# dongle.net
KiCad netlist of a schematic drawn in EAGLE
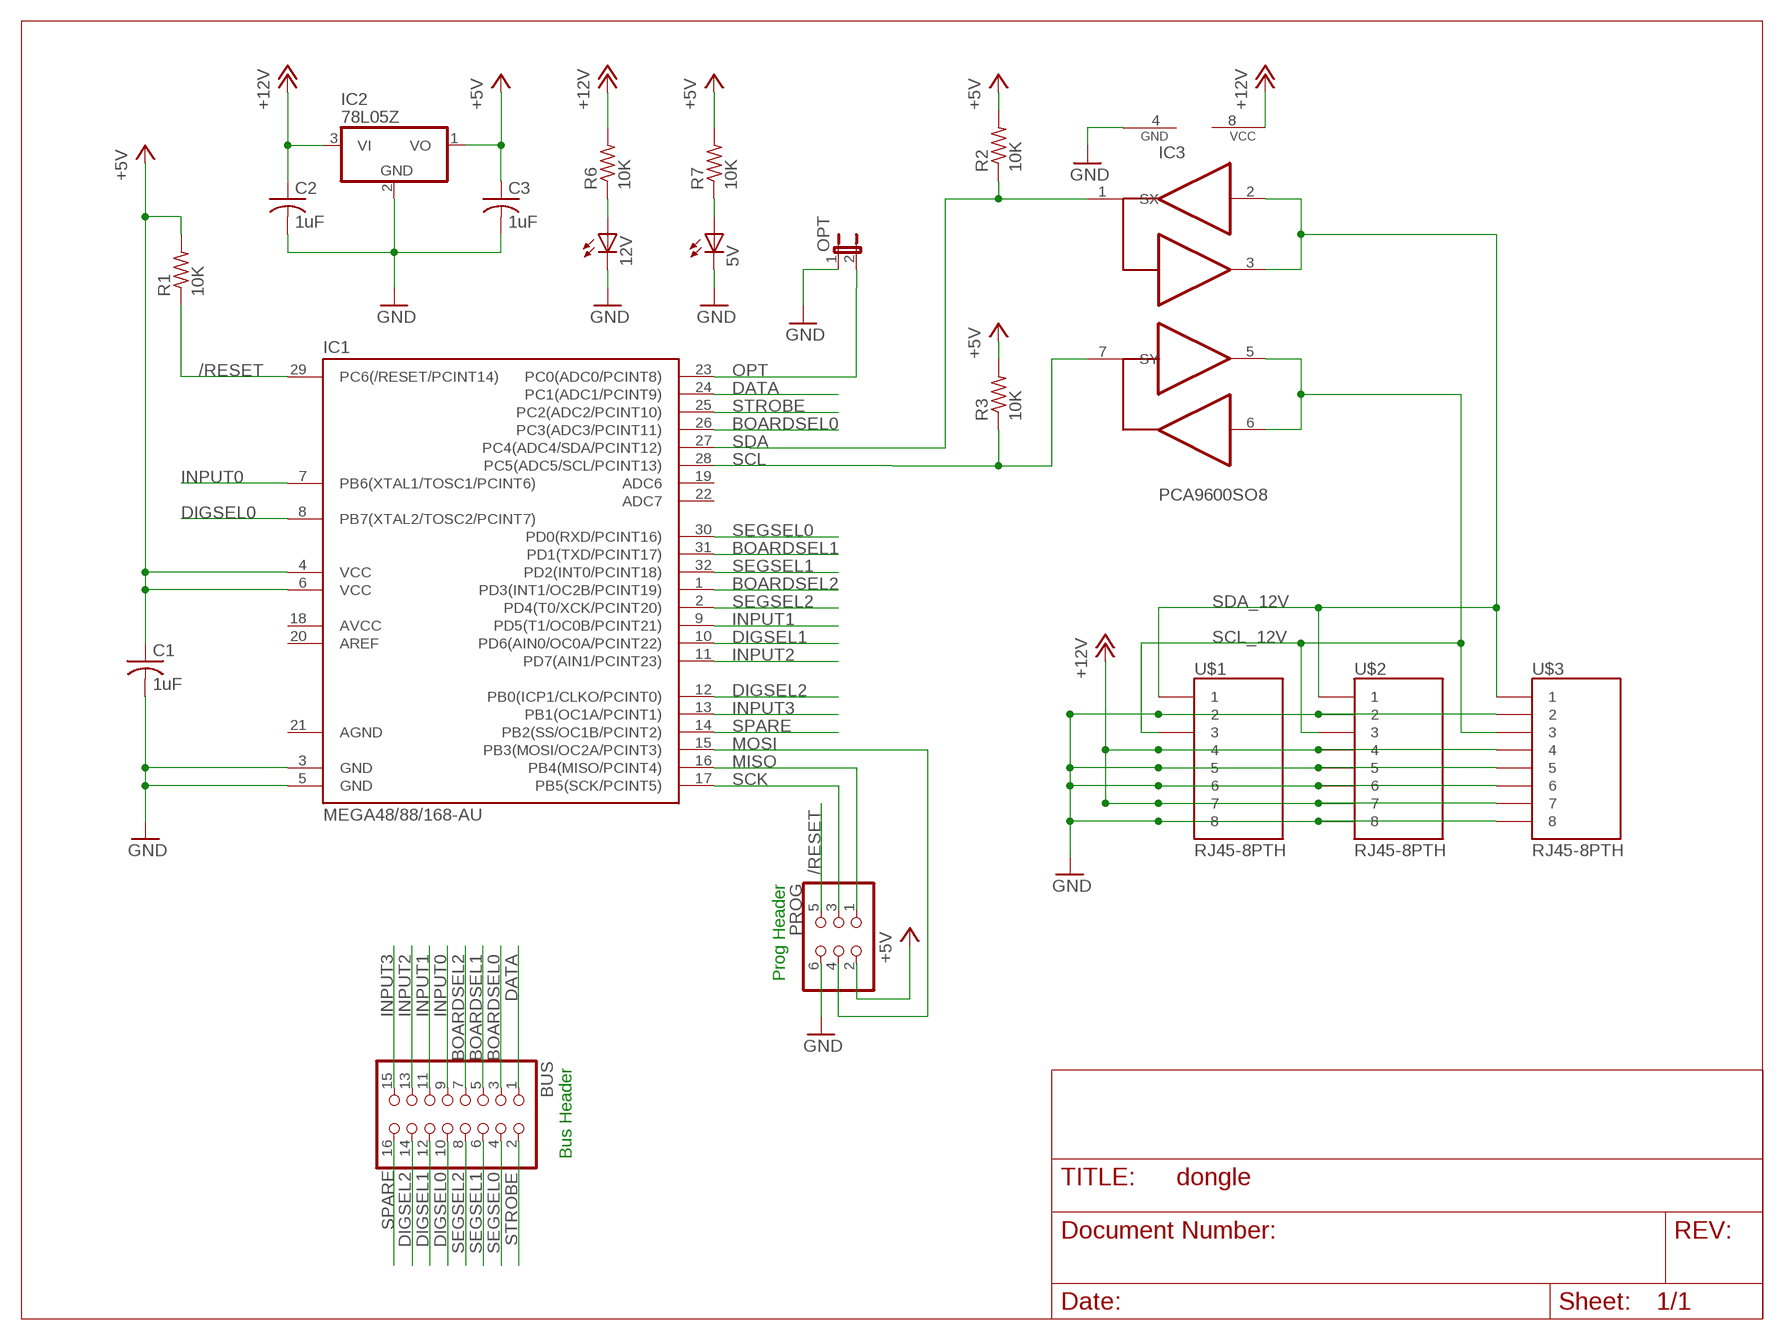
[diagram p0: schematic, sheet 1]

(export (version "E")
  (design (tool "Eeschema 10.0.6"))
  (components
    (comp (ref "5V")
      (value "LED3MM")
      (footprint "eagle-import:LED3MM")
      (libsource (lib "eagle-import") (part "LED3MM"))
    )
    (comp (ref "12V")
      (value "LED3MM")
      (footprint "eagle-import:LED3MM")
      (libsource (lib "eagle-import") (part "LED3MM"))
    )
    (comp (ref "BUS")
      (value "PINHD-2X8")
      (footprint "eagle-import:2X08")
      (libsource (lib "eagle-import") (part "PINHD-2X8"))
    )
    (comp (ref "C1")
      (value "1uF")
      (footprint "eagle-import:C025-025X050")
      (libsource (lib "eagle-import") (part "C-US025-025X050"))
    )
    (comp (ref "C2")
      (value "1uF")
      (footprint "eagle-import:C025-025X050")
      (libsource (lib "eagle-import") (part "C-US025-025X050"))
    )
    (comp (ref "C3")
      (value "1uF")
      (footprint "eagle-import:C025-025X050")
      (libsource (lib "eagle-import") (part "C-US025-025X050"))
    )
    (comp (ref "IC1")
      (value "MEGA48/88/168-AU")
      (footprint "eagle-import:TQFP32-08")
      (libsource (lib "eagle-import") (part "MEGA48/88/168-AU"))
    )
    (comp (ref "IC2")
      (value "78L05Z")
      (footprint "eagle-import:TO92")
      (libsource (lib "eagle-import") (part "78ZL05"))
    )
    (comp (ref "IC3")
      (value "PCA9600SO8")
      (footprint "eagle-import:SO08")
      (libsource (lib "eagle-import") (part "PCA9600SO8"))
    )
    (comp (ref "OPT")
      (value "JUMPER-2PTH")
      (footprint "eagle-import:1X02")
      (libsource (lib "eagle-import") (part "JUMPER-2PTH"))
    )
    (comp (ref "PROG")
      (value "PINHD-2X3")
      (footprint "eagle-import:2X03")
      (libsource (lib "eagle-import") (part "PINHD-2X3"))
    )
    (comp (ref "R1")
      (value "10K")
      (footprint "eagle-import:0204_5")
      (libsource (lib "eagle-import") (part "R-US_0204/5"))
    )
    (comp (ref "R2")
      (value "10K")
      (footprint "eagle-import:0204_5")
      (libsource (lib "eagle-import") (part "R-US_0204/5"))
    )
    (comp (ref "R3")
      (value "10K")
      (footprint "eagle-import:0204_5")
      (libsource (lib "eagle-import") (part "R-US_0204/5"))
    )
    (comp (ref "R6")
      (value "10K")
      (footprint "eagle-import:0204_5")
      (libsource (lib "eagle-import") (part "R-US_0204/5"))
    )
    (comp (ref "R7")
      (value "10K")
      (footprint "eagle-import:0204_5")
      (libsource (lib "eagle-import") (part "R-US_0204/5"))
    )
    (comp (ref "U$1")
      (value "RJ45-8PTH")
      (footprint "eagle-import:RJ45-8")
      (libsource (lib "eagle-import") (part "RJ45-8PTH"))
    )
    (comp (ref "U$2")
      (value "RJ45-8PTH")
      (footprint "eagle-import:RJ45-8")
      (libsource (lib "eagle-import") (part "RJ45-8PTH"))
    )
    (comp (ref "U$3")
      (value "RJ45-8PTH")
      (footprint "eagle-import:RJ45-8")
      (libsource (lib "eagle-import") (part "RJ45-8PTH"))
    )
  )
  (nets
    (net (code "1") (name "+5V") (class "Default")
      (node (ref "C1") (pin "1") (pinfunction "1_1") (pintype "passive"))
      (node (ref "C3") (pin "1") (pinfunction "1_1") (pintype "passive"))
      (node (ref "IC1") (pin "4") (pinfunction "VCC_4") (pintype "power_in"))
      (node (ref "IC1") (pin "6") (pinfunction "VCC_6") (pintype "power_in"))
      (node (ref "IC2") (pin "1") (pinfunction "VO_1") (pintype "passive"))
      (node (ref "PROG") (pin "2") (pinfunction "2_2") (pintype "passive"))
      (node (ref "R1") (pin "2") (pinfunction "2_2") (pintype "passive"))
      (node (ref "R2") (pin "2") (pinfunction "2_2") (pintype "passive"))
      (node (ref "R3") (pin "2") (pinfunction "2_2") (pintype "passive"))
      (node (ref "R7") (pin "2") (pinfunction "2_2") (pintype "passive"))
    )
    (net (code "2") (name "+12V") (class "Default")
      (node (ref "C2") (pin "1") (pinfunction "1_1") (pintype "passive"))
      (node (ref "IC2") (pin "3") (pinfunction "VI_3") (pintype "input"))
      (node (ref "IC3") (pin "8") (pinfunction "VCC_8") (pintype "power_in"))
      (node (ref "R6") (pin "2") (pinfunction "2_2") (pintype "passive"))
      (node (ref "U$1") (pin "4") (pinfunction "4_4") (pintype "bidirectional"))
      (node (ref "U$1") (pin "7") (pinfunction "7_7") (pintype "bidirectional"))
      (node (ref "U$2") (pin "4") (pinfunction "4_4") (pintype "bidirectional"))
      (node (ref "U$2") (pin "7") (pinfunction "7_7") (pintype "bidirectional"))
      (node (ref "U$3") (pin "4") (pinfunction "4_4") (pintype "bidirectional"))
      (node (ref "U$3") (pin "7") (pinfunction "7_7") (pintype "bidirectional"))
    )
    (net (code "3") (name "/AGND") (class "Default")
      (node (ref "IC1") (pin "21") (pinfunction "AGND_21") (pintype "power_in"))
    )
    (net (code "4") (name "/BOARDSEL0") (class "Default")
      (node (ref "BUS") (pin "3") (pinfunction "3_3") (pintype "passive"))
      (node (ref "IC1") (pin "26") (pinfunction "PC3(ADC3/PCINT11)_26") (pintype "bidirectional"))
    )
    (net (code "5") (name "/BOARDSEL1") (class "Default")
      (node (ref "BUS") (pin "5") (pinfunction "5_5") (pintype "passive"))
      (node (ref "IC1") (pin "31") (pinfunction "PD1(TXD/PCINT17)_31") (pintype "bidirectional"))
    )
    (net (code "6") (name "/BOARDSEL2") (class "Default")
      (node (ref "BUS") (pin "7") (pinfunction "7_7") (pintype "passive"))
      (node (ref "IC1") (pin "1") (pinfunction "PD3(INT1/OC2B/PCINT19)_1") (pintype "bidirectional"))
    )
    (net (code "7") (name "/DATA") (class "Default")
      (node (ref "BUS") (pin "1") (pinfunction "1_1") (pintype "passive"))
      (node (ref "IC1") (pin "24") (pinfunction "PC1(ADC1/PCINT9)_24") (pintype "bidirectional"))
    )
    (net (code "8") (name "/DIGSEL0") (class "Default")
      (node (ref "BUS") (pin "10") (pinfunction "10_10") (pintype "passive"))
      (node (ref "IC1") (pin "8") (pinfunction "PB7(XTAL2/TOSC2/PCINT7)_8") (pintype "bidirectional"))
    )
    (net (code "9") (name "/DIGSEL1") (class "Default")
      (node (ref "BUS") (pin "12") (pinfunction "12_12") (pintype "passive"))
      (node (ref "IC1") (pin "10") (pinfunction "PD6(AIN0/OC0A/PCINT22)_10") (pintype "bidirectional"))
    )
    (net (code "10") (name "/DIGSEL2") (class "Default")
      (node (ref "BUS") (pin "14") (pinfunction "14_14") (pintype "passive"))
      (node (ref "IC1") (pin "12") (pinfunction "PB0(ICP1/CLKO/PCINT0)_12") (pintype "bidirectional"))
    )
    (net (code "11") (name "/INPUT0") (class "Default")
      (node (ref "BUS") (pin "9") (pinfunction "9_9") (pintype "passive"))
      (node (ref "IC1") (pin "7") (pinfunction "PB6(XTAL1/TOSC1/PCINT6)_7") (pintype "bidirectional"))
    )
    (net (code "12") (name "/INPUT1") (class "Default")
      (node (ref "BUS") (pin "11") (pinfunction "11_11") (pintype "passive"))
      (node (ref "IC1") (pin "9") (pinfunction "PD5(T1/OC0B/PCINT21)_9") (pintype "bidirectional"))
    )
    (net (code "13") (name "/INPUT2") (class "Default")
      (node (ref "BUS") (pin "13") (pinfunction "13_13") (pintype "passive"))
      (node (ref "IC1") (pin "11") (pinfunction "PD7(AIN1/PCINT23)_11") (pintype "bidirectional"))
    )
    (net (code "14") (name "/INPUT3") (class "Default")
      (node (ref "BUS") (pin "15") (pinfunction "15_15") (pintype "passive"))
      (node (ref "IC1") (pin "13") (pinfunction "PB1(OC1A/PCINT1)_13") (pintype "bidirectional"))
    )
    (net (code "15") (name "/MISO") (class "Default")
      (node (ref "IC1") (pin "16") (pinfunction "PB4(MISO/PCINT4)_16") (pintype "bidirectional"))
      (node (ref "PROG") (pin "1") (pinfunction "1_1") (pintype "passive"))
    )
    (net (code "16") (name "/MOSI") (class "Default")
      (node (ref "IC1") (pin "15") (pinfunction "PB3(MOSI/OC2A/PCINT3)_15") (pintype "bidirectional"))
      (node (ref "PROG") (pin "4") (pinfunction "4_4") (pintype "passive"))
    )
    (net (code "17") (name "/OPT") (class "Default")
      (node (ref "IC1") (pin "23") (pinfunction "PC0(ADC0/PCINT8)_23") (pintype "bidirectional"))
      (node (ref "OPT") (pin "2") (pinfunction "2_2") (pintype "passive"))
    )
    (net (code "18") (name "/SCK") (class "Default")
      (node (ref "IC1") (pin "17") (pinfunction "PB5(SCK/PCINT5)_17") (pintype "bidirectional"))
      (node (ref "PROG") (pin "3") (pinfunction "3_3") (pintype "passive"))
    )
    (net (code "19") (name "/SCL") (class "Default")
      (node (ref "IC1") (pin "28") (pinfunction "PC5(ADC5/SCL/PCINT13)_28") (pintype "bidirectional"))
      (node (ref "IC3") (pin "7") (pinfunction "SY_7") (pintype "bidirectional"))
      (node (ref "R3") (pin "1") (pinfunction "1_1") (pintype "passive"))
    )
    (net (code "20") (name "/SCL_12V") (class "Default")
      (node (ref "IC3") (pin "5") (pinfunction "TY_5") (pintype "output"))
      (node (ref "IC3") (pin "6") (pinfunction "RY_6") (pintype "input"))
      (node (ref "U$1") (pin "3") (pinfunction "3_3") (pintype "bidirectional"))
      (node (ref "U$2") (pin "3") (pinfunction "3_3") (pintype "bidirectional"))
      (node (ref "U$3") (pin "3") (pinfunction "3_3") (pintype "bidirectional"))
    )
    (net (code "21") (name "/SDA") (class "Default")
      (node (ref "IC1") (pin "27") (pinfunction "PC4(ADC4/SDA/PCINT12)_27") (pintype "bidirectional"))
      (node (ref "IC3") (pin "1") (pinfunction "SX_1") (pintype "bidirectional"))
      (node (ref "R2") (pin "1") (pinfunction "1_1") (pintype "passive"))
    )
    (net (code "22") (name "/SDA_12V") (class "Default")
      (node (ref "IC3") (pin "2") (pinfunction "RX_2") (pintype "input"))
      (node (ref "IC3") (pin "3") (pinfunction "TX_3") (pintype "output"))
      (node (ref "U$1") (pin "1") (pinfunction "1_1") (pintype "bidirectional"))
      (node (ref "U$2") (pin "1") (pinfunction "1_1") (pintype "bidirectional"))
      (node (ref "U$3") (pin "1") (pinfunction "1_1") (pintype "bidirectional"))
    )
    (net (code "23") (name "/SEGSEL0") (class "Default")
      (node (ref "BUS") (pin "4") (pinfunction "4_4") (pintype "passive"))
      (node (ref "IC1") (pin "30") (pinfunction "PD0(RXD/PCINT16)_30") (pintype "bidirectional"))
    )
    (net (code "24") (name "/SEGSEL1") (class "Default")
      (node (ref "BUS") (pin "6") (pinfunction "6_6") (pintype "passive"))
      (node (ref "IC1") (pin "32") (pinfunction "PD2(INT0/PCINT18)_32") (pintype "bidirectional"))
    )
    (net (code "25") (name "/SEGSEL2") (class "Default")
      (node (ref "BUS") (pin "8") (pinfunction "8_8") (pintype "passive"))
      (node (ref "IC1") (pin "2") (pinfunction "PD4(T0/XCK/PCINT20)_2") (pintype "bidirectional"))
    )
    (net (code "26") (name "/SPARE") (class "Default")
      (node (ref "BUS") (pin "16") (pinfunction "16_16") (pintype "passive"))
      (node (ref "IC1") (pin "14") (pinfunction "PB2(SS/OC1B/PCINT2)_14") (pintype "bidirectional"))
    )
    (net (code "27") (name "/STROBE") (class "Default")
      (node (ref "BUS") (pin "2") (pinfunction "2_2") (pintype "passive"))
      (node (ref "IC1") (pin "25") (pinfunction "PC2(ADC2/PCINT10)_25") (pintype "bidirectional"))
    )
    (net (code "28") (name "/{slash}RESET") (class "Default")
      (node (ref "IC1") (pin "29") (pinfunction "PC6(/RESET/PCINT14)_29") (pintype "bidirectional"))
      (node (ref "PROG") (pin "5") (pinfunction "5_5") (pintype "passive"))
      (node (ref "R1") (pin "1") (pinfunction "1_1") (pintype "passive"))
    )
    (net (code "29") (name "GND") (class "Default")
      (node (ref "12V") (pin "K") (pinfunction "C_K") (pintype "passive"))
      (node (ref "5V") (pin "K") (pinfunction "C_K") (pintype "passive"))
      (node (ref "C1") (pin "2") (pinfunction "2_2") (pintype "passive"))
      (node (ref "C2") (pin "2") (pinfunction "2_2") (pintype "passive"))
      (node (ref "C3") (pin "2") (pinfunction "2_2") (pintype "passive"))
      (node (ref "IC1") (pin "3") (pinfunction "GND_3") (pintype "power_in"))
      (node (ref "IC1") (pin "5") (pinfunction "GND_5") (pintype "power_in"))
      (node (ref "IC2") (pin "2") (pinfunction "GND_2") (pintype "passive"))
      (node (ref "IC3") (pin "4") (pinfunction "GND_4") (pintype "power_in"))
      (node (ref "OPT") (pin "1") (pinfunction "1_1") (pintype "passive"))
      (node (ref "PROG") (pin "6") (pinfunction "6_6") (pintype "passive"))
      (node (ref "U$1") (pin "2") (pinfunction "2_2") (pintype "bidirectional"))
      (node (ref "U$1") (pin "5") (pinfunction "5_5") (pintype "bidirectional"))
      (node (ref "U$1") (pin "6") (pinfunction "6_6") (pintype "bidirectional"))
      (node (ref "U$1") (pin "8") (pinfunction "8_8") (pintype "bidirectional"))
      (node (ref "U$2") (pin "2") (pinfunction "2_2") (pintype "bidirectional"))
      (node (ref "U$2") (pin "5") (pinfunction "5_5") (pintype "bidirectional"))
      (node (ref "U$2") (pin "6") (pinfunction "6_6") (pintype "bidirectional"))
      (node (ref "U$2") (pin "8") (pinfunction "8_8") (pintype "bidirectional"))
      (node (ref "U$3") (pin "2") (pinfunction "2_2") (pintype "bidirectional"))
      (node (ref "U$3") (pin "5") (pinfunction "5_5") (pintype "bidirectional"))
      (node (ref "U$3") (pin "6") (pinfunction "6_6") (pintype "bidirectional"))
      (node (ref "U$3") (pin "8") (pinfunction "8_8") (pintype "bidirectional"))
    )
    (net (code "30") (name "Net-(5V-PadA)") (class "Default")
      (node (ref "5V") (pin "A") (pinfunction "A_A") (pintype "passive"))
      (node (ref "R7") (pin "1") (pinfunction "1_1") (pintype "passive"))
    )
    (net (code "31") (name "Net-(12V-PadA)") (class "Default")
      (node (ref "12V") (pin "A") (pinfunction "A_A") (pintype "passive"))
      (node (ref "R6") (pin "1") (pinfunction "1_1") (pintype "passive"))
    )
    (net (code "32") (name "unconnected-(IC1-ADC6-Pad19)") (class "Default")
      (node (ref "IC1") (pin "19") (pinfunction "ADC6_19") (pintype "passive"))
    )
    (net (code "33") (name "unconnected-(IC1-ADC7-Pad22)") (class "Default")
      (node (ref "IC1") (pin "22") (pinfunction "ADC7_22") (pintype "passive"))
    )
    (net (code "34") (name "unconnected-(IC1-AREF-Pad20)") (class "Default")
      (node (ref "IC1") (pin "20") (pinfunction "AREF_20") (pintype "passive"))
    )
    (net (code "35") (name "unconnected-(IC1-AVCC-Pad18)") (class "Default")
      (node (ref "IC1") (pin "18") (pinfunction "AVCC_18") (pintype "passive"))
    )
  )
)
